# EMSBUS.net
KiCad netlist of a schematic drawn in EAGLE
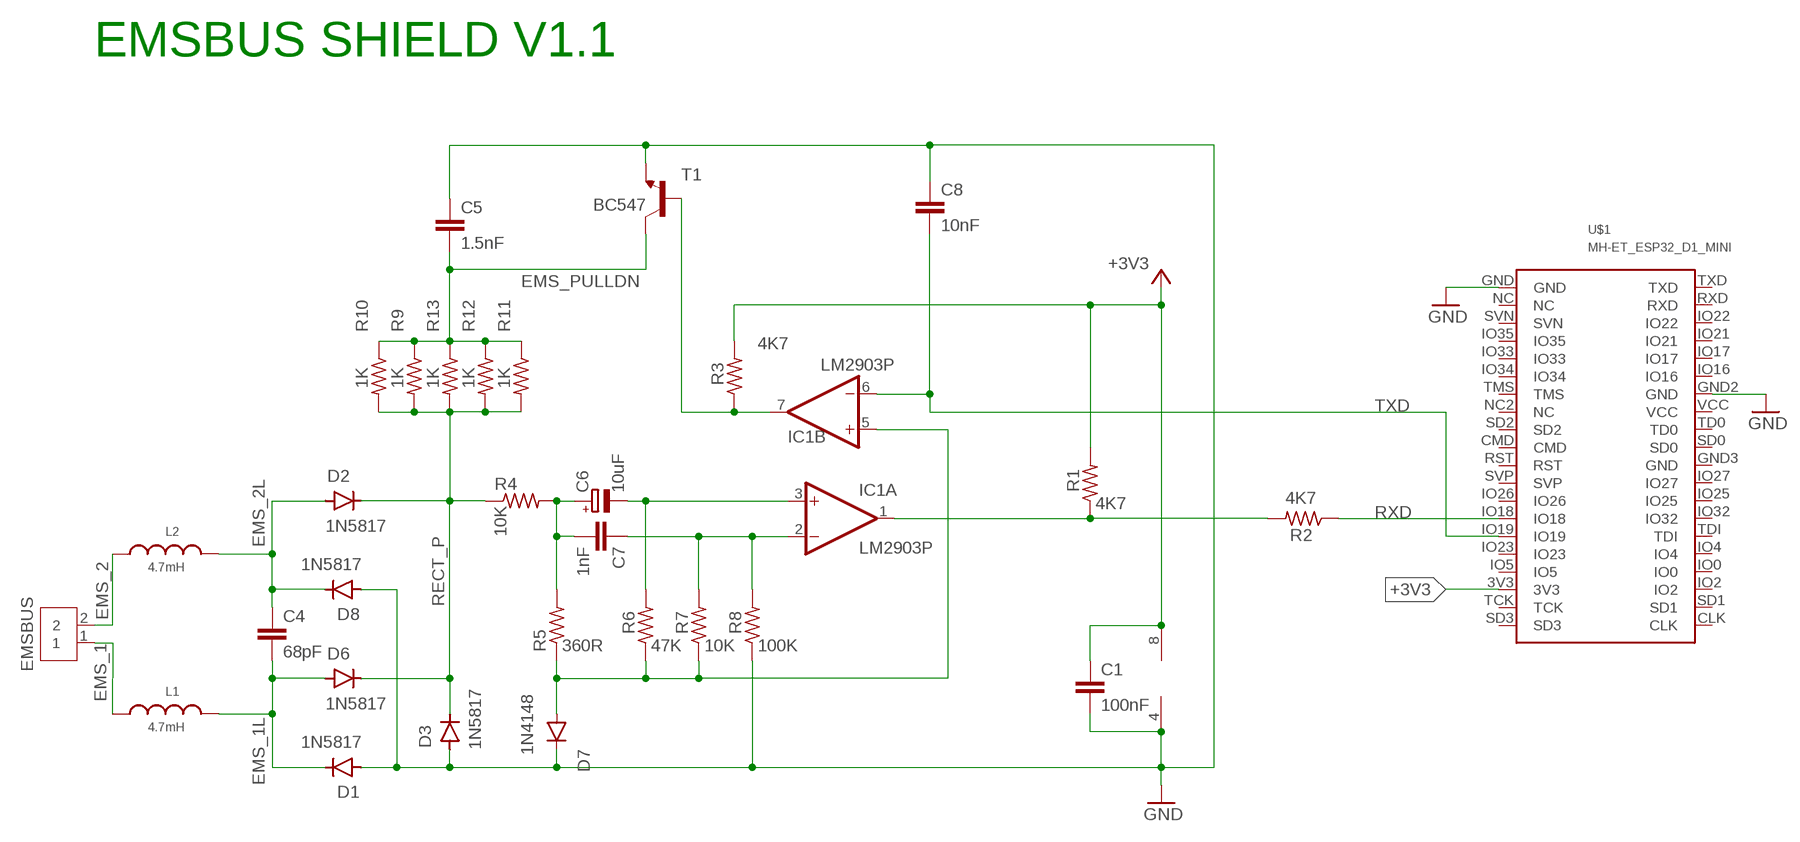
[diagram p0: schematic, sheet 1]

(export (version "E")
  (design (tool "Eeschema 10.0.6"))
  (components
    (comp (ref "C1")
      (value "100nF")
      (footprint "eagle-import:CAP-PTH-2.54")
      (libsource (lib "eagle-import") (part "22PF-PTH-2.54MM-200V-5%"))
    )
    (comp (ref "C4")
      (value "68pF")
      (footprint "eagle-import:CAP-PTH-2.54")
      (libsource (lib "eagle-import") (part "22PF-PTH-2.54MM-200V-5%"))
    )
    (comp (ref "C5")
      (value "1.5nF")
      (footprint "eagle-import:CAP-PTH-2.54")
      (libsource (lib "eagle-import") (part "22PF-PTH-2.54MM-200V-5%"))
    )
    (comp (ref "C6")
      (value "10uF")
      (footprint "eagle-import:E5-8,5")
      (libsource (lib "eagle-import") (part "CPOL-EUE5-8.5"))
    )
    (comp (ref "C7")
      (value "1nF")
      (footprint "eagle-import:CAP-PTH-2.54")
      (libsource (lib "eagle-import") (part "22PF-PTH-2.54MM-200V-5%"))
    )
    (comp (ref "C8")
      (value "10nF")
      (footprint "eagle-import:CAP-PTH-2.54")
      (libsource (lib "eagle-import") (part "22PF-PTH-2.54MM-200V-5%"))
    )
    (comp (ref "D1")
      (value "1N5817")
      (footprint "eagle-import:DO-41")
      (fields
        (field (name "DIGIKEY_PART_NUMBER") "1N4007MSCT-ND")
        (field (name "MANUFACTURER") "Micro Commercial Co")
        (field (name "MPN") "1N4007")
        (field (name "CREATED_BY") "PCBLayout.com")
      )
      (libsource (lib "eagle-import") (part "1N4007"))
    )
    (comp (ref "D2")
      (value "1N5817")
      (footprint "eagle-import:DO-41")
      (fields
        (field (name "DIGIKEY_PART_NUMBER") "1N4007MSCT-ND")
        (field (name "MANUFACTURER") "Micro Commercial Co")
        (field (name "MPN") "1N4007")
        (field (name "CREATED_BY") "PCBLayout.com")
      )
      (libsource (lib "eagle-import") (part "1N4007"))
    )
    (comp (ref "D3")
      (value "1N5817")
      (footprint "eagle-import:DO-41")
      (fields
        (field (name "DIGIKEY_PART_NUMBER") "1N4007MSCT-ND")
        (field (name "MANUFACTURER") "Micro Commercial Co")
        (field (name "MPN") "1N4007")
        (field (name "CREATED_BY") "PCBLayout.com")
      )
      (libsource (lib "eagle-import") (part "1N4007"))
    )
    (comp (ref "D6")
      (value "1N5817")
      (footprint "eagle-import:DO-41")
      (fields
        (field (name "DIGIKEY_PART_NUMBER") "1N4007MSCT-ND")
        (field (name "MANUFACTURER") "Micro Commercial Co")
        (field (name "MPN") "1N4007")
        (field (name "CREATED_BY") "PCBLayout.com")
      )
      (libsource (lib "eagle-import") (part "1N4007"))
    )
    (comp (ref "D7")
      (value "1N4148")
      (footprint "eagle-import:DIODE-1N4148")
      (libsource (lib "eagle-import") (part "DIODE1N4148"))
    )
    (comp (ref "D8")
      (value "1N5817")
      (footprint "eagle-import:DO-41")
      (fields
        (field (name "DIGIKEY_PART_NUMBER") "1N4007MSCT-ND")
        (field (name "MANUFACTURER") "Micro Commercial Co")
        (field (name "MPN") "1N4007")
        (field (name "CREATED_BY") "PCBLayout.com")
      )
      (libsource (lib "eagle-import") (part "1N4007"))
    )
    (comp (ref "EMSBUS")
      (value "2828XX-2282837-2")
      (footprint "eagle-import:TERMBLK_508-2N")
      (fields (field (name "MANUFACTURER") "TE Connectivity") (field (name "MPN") "282837-2"))
      (libsource (lib "eagle-import") (part "2828XX-2282837-2"))
    )
    (comp (ref "IC1")
      (value "LM2903P")
      (footprint "eagle-import:DIL08")
      (fields (field (name "SPICEPREFIX") "J"))
      (libsource (lib "eagle-import") (part "TLC393P"))
    )
    (comp (ref "L1")
      (value "4.7mH")
      (footprint "eagle-import:WE-FAMI_8010_744750230030")
      (libsource (lib "eagle-import") (part "WE-FAMI_744750230030"))
    )
    (comp (ref "L2")
      (value "4.7mH")
      (footprint "eagle-import:WE-FAMI_8010_744750230030")
      (libsource (lib "eagle-import") (part "WE-FAMI_744750230030"))
    )
    (comp (ref "R1")
      (value "4K7")
      (footprint "eagle-import:0204_7")
      (libsource (lib "eagle-import") (part "R-US_0204/7"))
    )
    (comp (ref "R2")
      (value "4K7")
      (footprint "eagle-import:0204_7")
      (libsource (lib "eagle-import") (part "R-US_0204/7"))
    )
    (comp (ref "R3")
      (value "4K7")
      (footprint "eagle-import:0204_7")
      (libsource (lib "eagle-import") (part "R-US_0204/7"))
    )
    (comp (ref "R4")
      (value "10K")
      (footprint "eagle-import:0204_7")
      (libsource (lib "eagle-import") (part "R-US_0204/7"))
    )
    (comp (ref "R5")
      (value "360R")
      (footprint "eagle-import:0204_7")
      (libsource (lib "eagle-import") (part "R-US_0204/7"))
    )
    (comp (ref "R6")
      (value "47K")
      (footprint "eagle-import:0204_7")
      (libsource (lib "eagle-import") (part "R-US_0204/7"))
    )
    (comp (ref "R7")
      (value "10K")
      (footprint "eagle-import:0204_7")
      (libsource (lib "eagle-import") (part "R-US_0204/7"))
    )
    (comp (ref "R8")
      (value "100K")
      (footprint "eagle-import:0204_7")
      (libsource (lib "eagle-import") (part "R-US_0204/7"))
    )
    (comp (ref "R9")
      (value "1K")
      (footprint "eagle-import:0204_7")
      (libsource (lib "eagle-import") (part "R-US_0204/7"))
    )
    (comp (ref "R10")
      (value "1K")
      (footprint "eagle-import:0204_7")
      (libsource (lib "eagle-import") (part "R-US_0204/7"))
    )
    (comp (ref "R11")
      (value "1K")
      (footprint "eagle-import:0204_7")
      (libsource (lib "eagle-import") (part "R-US_0204/7"))
    )
    (comp (ref "R12")
      (value "1K")
      (footprint "eagle-import:0204_7")
      (libsource (lib "eagle-import") (part "R-US_0204/7"))
    )
    (comp (ref "R13")
      (value "1K")
      (footprint "eagle-import:0204_7")
      (libsource (lib "eagle-import") (part "R-US_0204/7"))
    )
    (comp (ref "T1")
      (value "BC547")
      (footprint "eagle-import:TO92")
      (libsource (lib "eagle-import") (part "BC547"))
    )
    (comp (ref "U$1")
      (value "MH-ET_ESP32_D1_MINI")
      (footprint "eagle-import:MH-ET_ESP32_D1_MINI")
      (libsource (lib "eagle-import") (part "MH-ET_ESP32_D1_MINI"))
    )
  )
  (nets
    (net (code "1") (name "+3V3") (class "Default")
      (node (ref "C1") (pin "1") (pinfunction "1_1") (pintype "passive"))
      (node (ref "IC1") (pin "8") (pinfunction "V+_8") (pintype "power_in"))
      (node (ref "R1") (pin "2") (pinfunction "2_2") (pintype "passive"))
      (node (ref "R3") (pin "2") (pinfunction "2_2") (pintype "passive"))
      (node (ref "U$1") (pin "3V3") (pinfunction "3V3_3V3") (pintype "bidirectional"))
    )
    (net (code "2") (name "/EMS_1") (class "Default")
      (node (ref "EMSBUS") (pin "1") (pinfunction "1_1") (pintype "bidirectional"))
      (node (ref "L1") (pin "1") (pinfunction "1_1") (pintype "passive"))
    )
    (net (code "3") (name "/EMS_1L") (class "Default")
      (node (ref "C4") (pin "2") (pinfunction "2_2") (pintype "passive"))
      (node (ref "D1") (pin "C") (pinfunction "C_C") (pintype "passive"))
      (node (ref "D6") (pin "A") (pinfunction "A_A") (pintype "passive"))
      (node (ref "L1") (pin "2") (pinfunction "2_2") (pintype "passive"))
    )
    (net (code "4") (name "/EMS_2") (class "Default")
      (node (ref "EMSBUS") (pin "2") (pinfunction "2_2") (pintype "bidirectional"))
      (node (ref "L2") (pin "1") (pinfunction "1_1") (pintype "passive"))
    )
    (net (code "5") (name "/EMS_2L") (class "Default")
      (node (ref "C4") (pin "1") (pinfunction "1_1") (pintype "passive"))
      (node (ref "D2") (pin "A") (pinfunction "A_A") (pintype "passive"))
      (node (ref "D8") (pin "C") (pinfunction "C_C") (pintype "passive"))
      (node (ref "L2") (pin "2") (pinfunction "2_2") (pintype "passive"))
    )
    (net (code "6") (name "/EMS_PULLDN") (class "Default")
      (node (ref "C5") (pin "2") (pinfunction "2_2") (pintype "passive"))
      (node (ref "R10") (pin "1") (pinfunction "1_1") (pintype "passive"))
      (node (ref "R11") (pin "1") (pinfunction "1_1") (pintype "passive"))
      (node (ref "R12") (pin "1") (pinfunction "1_1") (pintype "passive"))
      (node (ref "R13") (pin "1") (pinfunction "1_1") (pintype "passive"))
      (node (ref "R9") (pin "1") (pinfunction "1_1") (pintype "passive"))
      (node (ref "T1") (pin "3") (pinfunction "C_3") (pintype "passive"))
    )
    (net (code "7") (name "/RECT_P") (class "Default")
      (node (ref "D2") (pin "C") (pinfunction "C_C") (pintype "passive"))
      (node (ref "D3") (pin "C") (pinfunction "C_C") (pintype "passive"))
      (node (ref "D6") (pin "C") (pinfunction "C_C") (pintype "passive"))
      (node (ref "R10") (pin "2") (pinfunction "2_2") (pintype "passive"))
      (node (ref "R11") (pin "2") (pinfunction "2_2") (pintype "passive"))
      (node (ref "R12") (pin "2") (pinfunction "2_2") (pintype "passive"))
      (node (ref "R13") (pin "2") (pinfunction "2_2") (pintype "passive"))
      (node (ref "R4") (pin "1") (pinfunction "1_1") (pintype "passive"))
      (node (ref "R9") (pin "2") (pinfunction "2_2") (pintype "passive"))
    )
    (net (code "8") (name "/RXD") (class "Default")
      (node (ref "R2") (pin "1") (pinfunction "1_1") (pintype "passive"))
      (node (ref "U$1") (pin "IO18") (pinfunction "IO18_IO18") (pintype "bidirectional"))
    )
    (net (code "9") (name "/TXD") (class "Default")
      (node (ref "C8") (pin "2") (pinfunction "2_2") (pintype "passive"))
      (node (ref "IC1") (pin "6") (pinfunction "-IN_6") (pintype "input"))
      (node (ref "U$1") (pin "IO19") (pinfunction "IO19_IO19") (pintype "bidirectional"))
    )
    (net (code "10") (name "GND") (class "Default")
      (node (ref "C1") (pin "2") (pinfunction "2_2") (pintype "passive"))
      (node (ref "C5") (pin "1") (pinfunction "1_1") (pintype "passive"))
      (node (ref "C8") (pin "1") (pinfunction "1_1") (pintype "passive"))
      (node (ref "D1") (pin "A") (pinfunction "A_A") (pintype "passive"))
      (node (ref "D3") (pin "A") (pinfunction "A_A") (pintype "passive"))
      (node (ref "D7") (pin "C") (pinfunction "C_C") (pintype "passive"))
      (node (ref "D8") (pin "A") (pinfunction "A_A") (pintype "passive"))
      (node (ref "IC1") (pin "4") (pinfunction "V-_4") (pintype "power_in"))
      (node (ref "R8") (pin "1") (pinfunction "1_1") (pintype "passive"))
      (node (ref "T1") (pin "1") (pinfunction "E_1") (pintype "passive"))
      (node (ref "U$1") (pin "GND") (pinfunction "GND_GND") (pintype "bidirectional"))
      (node (ref "U$1") (pin "GND2") (pinfunction "GND_GND2") (pintype "bidirectional"))
    )
    (net (code "11") (name "Net-(C6-Pad+)") (class "Default")
      (node (ref "C6") (pin "+") (pinfunction "+_+") (pintype "passive"))
      (node (ref "C7") (pin "2") (pinfunction "2_2") (pintype "passive"))
      (node (ref "R4") (pin "2") (pinfunction "2_2") (pintype "passive"))
      (node (ref "R5") (pin "2") (pinfunction "2_2") (pintype "passive"))
    )
    (net (code "12") (name "Net-(IC1A-+IN)") (class "Default")
      (node (ref "C6") (pin "-") (pinfunction "-_-") (pintype "passive"))
      (node (ref "IC1") (pin "3") (pinfunction "+IN_3") (pintype "input"))
      (node (ref "R6") (pin "2") (pinfunction "2_2") (pintype "passive"))
    )
    (net (code "13") (name "Net-(IC1A--IN)") (class "Default")
      (node (ref "C7") (pin "1") (pinfunction "1_1") (pintype "passive"))
      (node (ref "IC1") (pin "2") (pinfunction "-IN_2") (pintype "input"))
      (node (ref "R7") (pin "2") (pinfunction "2_2") (pintype "passive"))
      (node (ref "R8") (pin "2") (pinfunction "2_2") (pintype "passive"))
    )
    (net (code "14") (name "Net-(IC1A-OUT)") (class "Default")
      (node (ref "IC1") (pin "1") (pinfunction "OUT_1") (pintype "output"))
      (node (ref "R1") (pin "1") (pinfunction "1_1") (pintype "passive"))
      (node (ref "R2") (pin "2") (pinfunction "2_2") (pintype "passive"))
    )
    (net (code "15") (name "Net-(IC1B-+IN)") (class "Default")
      (node (ref "D7") (pin "A") (pinfunction "A_A") (pintype "passive"))
      (node (ref "IC1") (pin "5") (pinfunction "+IN_5") (pintype "input"))
      (node (ref "R5") (pin "1") (pinfunction "1_1") (pintype "passive"))
      (node (ref "R6") (pin "1") (pinfunction "1_1") (pintype "passive"))
      (node (ref "R7") (pin "1") (pinfunction "1_1") (pintype "passive"))
    )
    (net (code "16") (name "Net-(IC1B-OUT)") (class "Default")
      (node (ref "IC1") (pin "7") (pinfunction "OUT_7") (pintype "output"))
      (node (ref "R3") (pin "1") (pinfunction "1_1") (pintype "passive"))
      (node (ref "T1") (pin "2") (pinfunction "B_2") (pintype "passive"))
    )
    (net (code "17") (name "unconnected-(U$1-GND-PadGND3)") (class "Default")
      (node (ref "U$1") (pin "GND3") (pinfunction "GND_GND3") (pintype "bidirectional"))
    )
    (net (code "18") (name "unconnected-(U$1-NC-PadNC2)") (class "Default")
      (node (ref "U$1") (pin "NC2") (pinfunction "NC_NC2") (pintype "bidirectional"))
    )
    (net (code "19") (name "unconnected-(U$1-PadCLK)") (class "Default")
      (node (ref "U$1") (pin "CLK") (pinfunction "CLK_CLK") (pintype "bidirectional"))
    )
    (net (code "20") (name "unconnected-(U$1-PadCMD)") (class "Default")
      (node (ref "U$1") (pin "CMD") (pinfunction "CMD_CMD") (pintype "bidirectional"))
    )
    (net (code "21") (name "unconnected-(U$1-PadIO0)") (class "Default")
      (node (ref "U$1") (pin "IO0") (pinfunction "IO0_IO0") (pintype "bidirectional"))
    )
    (net (code "22") (name "unconnected-(U$1-PadIO2)") (class "Default")
      (node (ref "U$1") (pin "IO2") (pinfunction "IO2_IO2") (pintype "bidirectional"))
    )
    (net (code "23") (name "unconnected-(U$1-PadIO4)") (class "Default")
      (node (ref "U$1") (pin "IO4") (pinfunction "IO4_IO4") (pintype "bidirectional"))
    )
    (net (code "24") (name "unconnected-(U$1-PadIO5)") (class "Default")
      (node (ref "U$1") (pin "IO5") (pinfunction "IO5_IO5") (pintype "bidirectional"))
    )
    (net (code "25") (name "unconnected-(U$1-PadIO16)") (class "Default")
      (node (ref "U$1") (pin "IO16") (pinfunction "IO16_IO16") (pintype "bidirectional"))
    )
    (net (code "26") (name "unconnected-(U$1-PadIO17)") (class "Default")
      (node (ref "U$1") (pin "IO17") (pinfunction "IO17_IO17") (pintype "bidirectional"))
    )
    (net (code "27") (name "unconnected-(U$1-PadIO21)") (class "Default")
      (node (ref "U$1") (pin "IO21") (pinfunction "IO21_IO21") (pintype "bidirectional"))
    )
    (net (code "28") (name "unconnected-(U$1-PadIO22)") (class "Default")
      (node (ref "U$1") (pin "IO22") (pinfunction "IO22_IO22") (pintype "bidirectional"))
    )
    (net (code "29") (name "unconnected-(U$1-PadIO23)") (class "Default")
      (node (ref "U$1") (pin "IO23") (pinfunction "IO23_IO23") (pintype "bidirectional"))
    )
    (net (code "30") (name "unconnected-(U$1-PadIO25)") (class "Default")
      (node (ref "U$1") (pin "IO25") (pinfunction "IO25_IO25") (pintype "bidirectional"))
    )
    (net (code "31") (name "unconnected-(U$1-PadIO26)") (class "Default")
      (node (ref "U$1") (pin "IO26") (pinfunction "IO26_IO26") (pintype "bidirectional"))
    )
    (net (code "32") (name "unconnected-(U$1-PadIO27)") (class "Default")
      (node (ref "U$1") (pin "IO27") (pinfunction "IO27_IO27") (pintype "bidirectional"))
    )
    (net (code "33") (name "unconnected-(U$1-PadIO32)") (class "Default")
      (node (ref "U$1") (pin "IO32") (pinfunction "IO32_IO32") (pintype "bidirectional"))
    )
    (net (code "34") (name "unconnected-(U$1-PadIO33)") (class "Default")
      (node (ref "U$1") (pin "IO33") (pinfunction "IO33_IO33") (pintype "bidirectional"))
    )
    (net (code "35") (name "unconnected-(U$1-PadIO34)") (class "Default")
      (node (ref "U$1") (pin "IO34") (pinfunction "IO34_IO34") (pintype "bidirectional"))
    )
    (net (code "36") (name "unconnected-(U$1-PadIO35)") (class "Default")
      (node (ref "U$1") (pin "IO35") (pinfunction "IO35_IO35") (pintype "bidirectional"))
    )
    (net (code "37") (name "unconnected-(U$1-PadNC)") (class "Default")
      (node (ref "U$1") (pin "NC") (pinfunction "NC_NC") (pintype "bidirectional"))
    )
    (net (code "38") (name "unconnected-(U$1-PadRST)") (class "Default")
      (node (ref "U$1") (pin "RST") (pinfunction "RST_RST") (pintype "bidirectional"))
    )
    (net (code "39") (name "unconnected-(U$1-PadRXD)") (class "Default")
      (node (ref "U$1") (pin "RXD") (pinfunction "RXD_RXD") (pintype "bidirectional"))
    )
    (net (code "40") (name "unconnected-(U$1-PadSD0)") (class "Default")
      (node (ref "U$1") (pin "SD0") (pinfunction "SD0_SD0") (pintype "bidirectional"))
    )
    (net (code "41") (name "unconnected-(U$1-PadSD1)") (class "Default")
      (node (ref "U$1") (pin "SD1") (pinfunction "SD1_SD1") (pintype "bidirectional"))
    )
    (net (code "42") (name "unconnected-(U$1-PadSD2)") (class "Default")
      (node (ref "U$1") (pin "SD2") (pinfunction "SD2_SD2") (pintype "bidirectional"))
    )
    (net (code "43") (name "unconnected-(U$1-PadSD3)") (class "Default")
      (node (ref "U$1") (pin "SD3") (pinfunction "SD3_SD3") (pintype "bidirectional"))
    )
    (net (code "44") (name "unconnected-(U$1-PadSVN)") (class "Default")
      (node (ref "U$1") (pin "SVN") (pinfunction "SVN_SVN") (pintype "bidirectional"))
    )
    (net (code "45") (name "unconnected-(U$1-PadSVP)") (class "Default")
      (node (ref "U$1") (pin "SVP") (pinfunction "SVP_SVP") (pintype "bidirectional"))
    )
    (net (code "46") (name "unconnected-(U$1-PadTCK)") (class "Default")
      (node (ref "U$1") (pin "TCK") (pinfunction "TCK_TCK") (pintype "bidirectional"))
    )
    (net (code "47") (name "unconnected-(U$1-PadTD0)") (class "Default")
      (node (ref "U$1") (pin "TD0") (pinfunction "TD0_TD0") (pintype "bidirectional"))
    )
    (net (code "48") (name "unconnected-(U$1-PadTDI)") (class "Default")
      (node (ref "U$1") (pin "TDI") (pinfunction "TDI_TDI") (pintype "bidirectional"))
    )
    (net (code "49") (name "unconnected-(U$1-PadTMS)") (class "Default")
      (node (ref "U$1") (pin "TMS") (pinfunction "TMS_TMS") (pintype "bidirectional"))
    )
    (net (code "50") (name "unconnected-(U$1-PadTXD)") (class "Default")
      (node (ref "U$1") (pin "TXD") (pinfunction "TXD_TXD") (pintype "bidirectional"))
    )
    (net (code "51") (name "unconnected-(U$1-PadVCC)") (class "Default")
      (node (ref "U$1") (pin "VCC") (pinfunction "VCC_VCC") (pintype "bidirectional"))
    )
  )
)
